# 12_MiniPcie-4G.net
KiCad netlist of a schematic drawn in Altium Designer
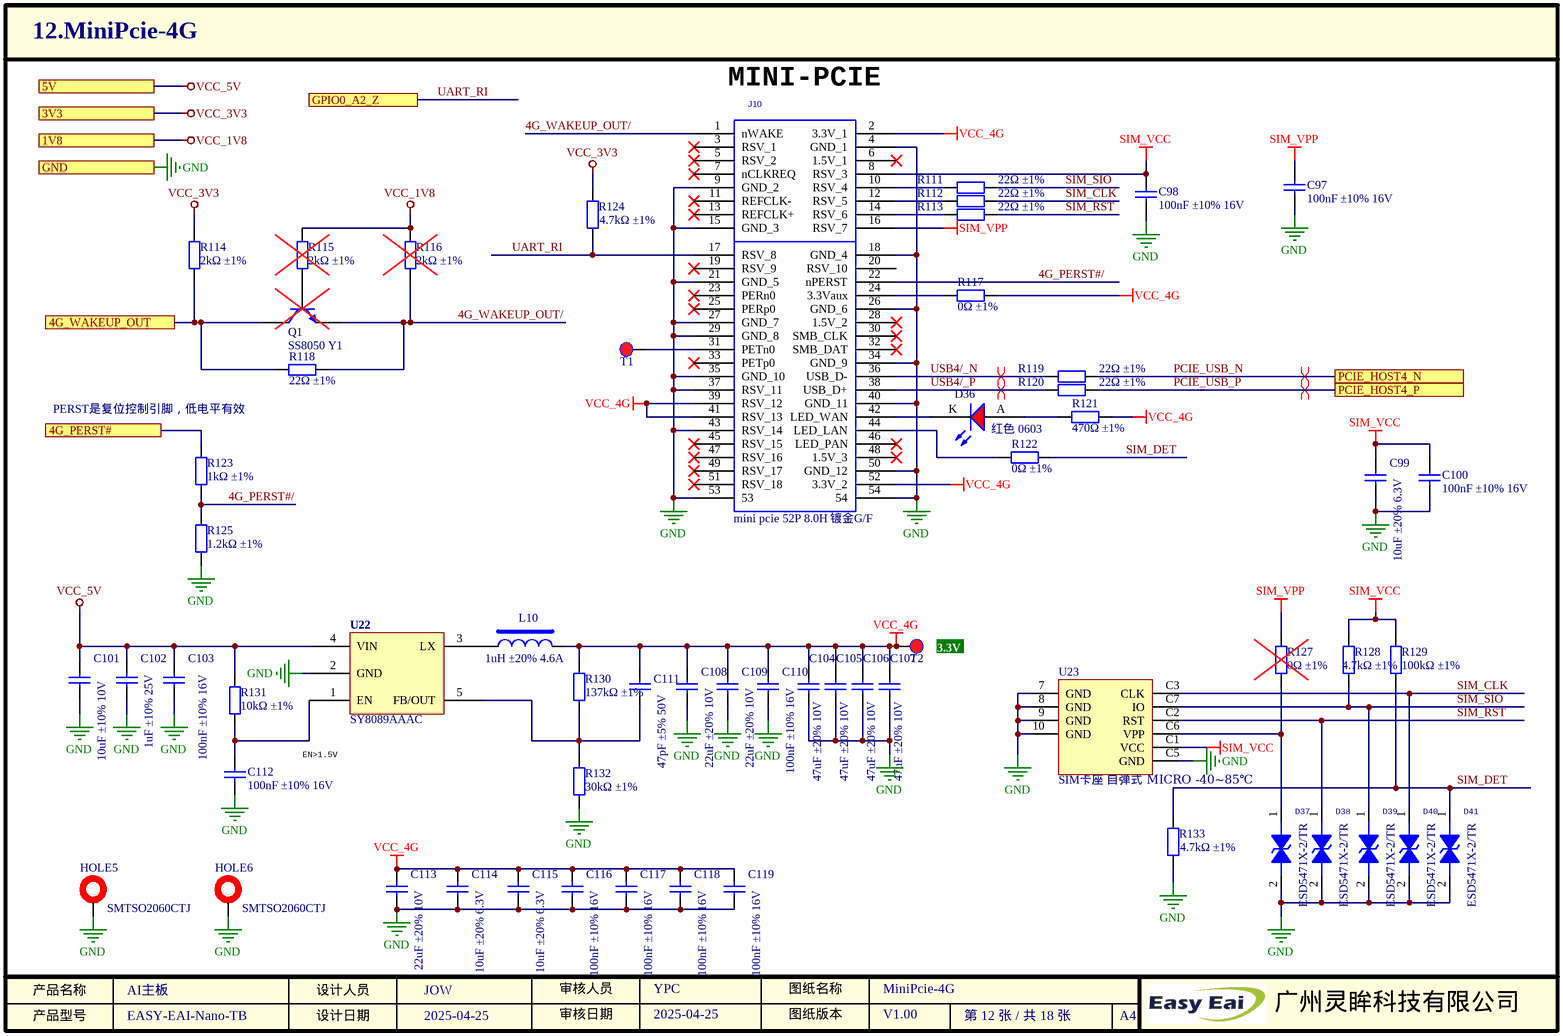
[diagram p0: 12.MiniPcie-4G.SchDoc]

(export (version "E")
  (design (tool "Eeschema 10.0.6"))
  (components
    (comp (ref "C97")
      (value "CL05B104KO5NNNC")
      (footprint "0402_C")
      (description "SPZL000259")
      (fields (field (name "描述") "100nF ±10% 16V"))
      (libsource (lib "CAP_EASY-EAI") (part "0402 100nF ±10% 16V"))
    )
    (comp (ref "C98")
      (value "CL05B104KO5NNNC")
      (footprint "0402_C")
      (description "SPZL000259")
      (fields (field (name "描述") "100nF ±10% 16V"))
      (libsource (lib "CAP_EASY-EAI") (part "0402 100nF ±10% 16V"))
    )
    (comp (ref "C99")
      (value "CL05A106MQ5NUNC")
      (footprint "0402_C")
      (description "SPZL000269")
      (fields (field (name "描述") "10uF ±20% 6.3V"))
      (libsource (lib "CAP_EASY-EAI") (part "0402 10uF ±20% 6.3V"))
    )
    (comp (ref "C100")
      (value "CL05B104KO5NNNC")
      (footprint "0402_C")
      (description "SPZL000259")
      (fields (field (name "描述") "100nF ±10% 16V"))
      (libsource (lib "CAP_EASY-EAI") (part "0402 100nF ±10% 16V"))
    )
    (comp (ref "C101")
      (value "CL10A106KP8NNNC")
      (footprint "0603_C")
      (description "SPZL000260")
      (fields (field (name "描述") "10uF ±10% 10V"))
      (libsource (lib "CAP_lexing") (part "0603 10uF ±10% 10V"))
    )
    (comp (ref "C102")
      (value "CL05A105KA5NQNC")
      (footprint "0402_C")
      (description "SPZL000337")
      (fields (field (name "描述") "1uF ±10% 25V"))
      (libsource (lib "CAP_lexing") (part "0402 1uF ±10% 25V"))
    )
    (comp (ref "C103")
      (value "CL05B104KO5NNNC")
      (footprint "0402_C")
      (description "SPZL000259")
      (fields (field (name "描述") "100nF ±10% 16V"))
      (libsource (lib "CAP_lexing") (part "0402 100nF ±10% 16V"))
    )
    (comp (ref "C104")
      (value "C2012X5R1A476MTJ00E")
      (footprint "0805_C")
      (description "SPZL001333")
      (fields (field (name "描述") "47uF ±20% 10V"))
      (libsource (lib "CAP_EASY-EAI") (part "0805 47uF ±20% 10V"))
    )
    (comp (ref "C105")
      (value "C2012X5R1A476MTJ00E")
      (footprint "0805_C")
      (description "SPZL001333")
      (fields (field (name "描述") "47uF ±20% 10V"))
      (libsource (lib "CAP_EASY-EAI") (part "0805 47uF ±20% 10V"))
    )
    (comp (ref "C106")
      (value "C2012X5R1A476MTJ00E")
      (footprint "0805_C")
      (description "SPZL001333")
      (fields (field (name "描述") "47uF ±20% 10V"))
      (libsource (lib "CAP_EASY-EAI") (part "0805 47uF ±20% 10V"))
    )
    (comp (ref "C107")
      (value "C2012X5R1A476MTJ00E")
      (footprint "0805_C")
      (description "SPZL001333")
      (fields (field (name "描述") "47uF ±20% 10V"))
      (libsource (lib "CAP_EASY-EAI") (part "0805 47uF ±20% 10V"))
    )
    (comp (ref "C108")
      (value "CL10A226MP8NUNE")
      (footprint "0603_C")
      (description "SPZL000315")
      (fields (field (name "描述") "22uF ±20% 10V"))
      (libsource (lib "CAP_lexing") (part "0603 22uF ±20% 10V"))
    )
    (comp (ref "C109")
      (value "CL10A226MP8NUNE")
      (footprint "0603_C")
      (description "SPZL000315")
      (fields (field (name "描述") "22uF ±20% 10V"))
      (libsource (lib "CAP_lexing") (part "0603 22uF ±20% 10V"))
    )
    (comp (ref "C110")
      (value "CL05B104KO5NNNC")
      (footprint "0402_C")
      (description "SPZL000259")
      (fields (field (name "描述") "100nF ±10% 16V"))
      (libsource (lib "CAP_lexing") (part "0402 100nF ±10% 16V"))
    )
    (comp (ref "C111")
      (value "NC/0402CG470J500NT")
      (footprint "0402_C")
      (description "SPZL000882")
      (fields (field (name "描述") "47pF ±5% 50V"))
      (libsource (lib "CAP_lexing") (part "0402 47pF ±5% 50V"))
    )
    (comp (ref "C112")
      (value "CL05B104KO5NNNC")
      (footprint "0402_C")
      (description "SPZL000259")
      (fields (field (name "描述") "100nF ±10% 16V"))
      (libsource (lib "CAP_lexing") (part "0402 100nF ±10% 16V"))
    )
    (comp (ref "C113")
      (value "CL10A226MP8NUNE")
      (footprint "0603_C")
      (description "SPZL000315")
      (fields (field (name "描述") "22uF ±20% 10V"))
      (libsource (lib "CAP_EASY-EAI") (part "0603 22uF ±20% 10V"))
    )
    (comp (ref "C114")
      (value "CL05A106MQ5NUNC")
      (footprint "0402_C")
      (description "SPZL000269")
      (fields (field (name "描述") "10uF ±20% 6.3V"))
      (libsource (lib "CAP_EASY-EAI") (part "0402 10uF ±20% 6.3V"))
    )
    (comp (ref "C115")
      (value "CL05A106MQ5NUNC")
      (footprint "0402_C")
      (description "SPZL000269")
      (fields (field (name "描述") "10uF ±20% 6.3V"))
      (libsource (lib "CAP_EASY-EAI") (part "0402 10uF ±20% 6.3V"))
    )
    (comp (ref "C116")
      (value "CL05B104KO5NNNC")
      (footprint "0402_C")
      (description "SPZL000259")
      (fields (field (name "描述") "100nF ±10% 16V"))
      (libsource (lib "CAP_lexing") (part "0402 100nF ±10% 16V"))
    )
    (comp (ref "C117")
      (value "CL05B104KO5NNNC")
      (footprint "0402_C")
      (description "SPZL000259")
      (fields (field (name "描述") "100nF ±10% 16V"))
      (libsource (lib "CAP_lexing") (part "0402 100nF ±10% 16V"))
    )
    (comp (ref "C118")
      (value "CL05B104KO5NNNC")
      (footprint "0402_C")
      (description "SPZL000259")
      (fields (field (name "描述") "100nF ±10% 16V"))
      (libsource (lib "CAP_lexing") (part "0402 100nF ±10% 16V"))
    )
    (comp (ref "C119")
      (value "CL05B104KO5NNNC")
      (footprint "0402_C")
      (description "SPZL000259")
      (fields (field (name "描述") "100nF ±10% 16V"))
      (libsource (lib "CAP_lexing") (part "0402 100nF ±10% 16V"))
    )
    (comp (ref "D36")
      (value "红色 0603")
      (footprint "0603_LED_S1")
      (description "SPZL000214")
      (fields (field (name "描述") "红色 0603"))
      (libsource (lib "LED_EASY-EAI") (part "红色 0603"))
    )
    (comp (ref "D37")
      (value "ESD5471X-2/TR")
      (footprint "FBP-02C")
      (description "SPZL000254")
      (fields (field (name "型号") "ESD5471X-2/TR"))
      (libsource (lib "ESD_EASY-EAI") (part "TVS ESD5471X-2/TR"))
    )
    (comp (ref "D38")
      (value "ESD5471X-2/TR")
      (footprint "FBP-02C")
      (description "SPZL000254")
      (fields (field (name "型号") "ESD5471X-2/TR"))
      (libsource (lib "ESD_EASY-EAI") (part "TVS ESD5471X-2/TR"))
    )
    (comp (ref "D39")
      (value "ESD5471X-2/TR")
      (footprint "FBP-02C")
      (description "SPZL000254")
      (fields (field (name "型号") "ESD5471X-2/TR"))
      (libsource (lib "ESD_EASY-EAI") (part "TVS ESD5471X-2/TR"))
    )
    (comp (ref "D40")
      (value "ESD5471X-2/TR")
      (footprint "FBP-02C")
      (description "SPZL000254")
      (fields (field (name "型号") "ESD5471X-2/TR"))
      (libsource (lib "ESD_EASY-EAI") (part "TVS ESD5471X-2/TR"))
    )
    (comp (ref "D41")
      (value "ESD5471X-2/TR")
      (footprint "FBP-02C")
      (description "SPZL000254")
      (fields (field (name "型号") "ESD5471X-2/TR"))
      (libsource (lib "ESD_EASY-EAI") (part "TVS ESD5471X-2/TR"))
    )
    (comp (ref "HOLE5")
      (value "SMTSO2060CTJ")
      (footprint "Mou Hole-373D600H-SMD")
      (description "SPZL000166")
      (fields (field (name "型号") "SMTSO2060CTJ"))
      (libsource (lib "Other_lexing") (part "螺柱 SMTSO-M2-6ET"))
    )
    (comp (ref "HOLE6")
      (value "SMTSO2060CTJ")
      (footprint "Mou Hole-373D600H-SMD")
      (description "SPZL000166")
      (fields (field (name "型号") "SMTSO2060CTJ"))
      (libsource (lib "Other_lexing") (part "螺柱 SMTSO-M2-6ET"))
    )
    (comp (ref "J10")
      (value "91304-80-052R2")
      (footprint "MEDC52-32F-PCIE-LOCK-L")
      (description "SPZL000136")
      (fields (field (name "描述") "mini pcie 52P 8.0H 镀金G/F"))
      (libsource (lib "Connector_EASY-EAI") (part "mini pcie 52P 8.0H 镀金G/F"))
    )
    (comp (ref "L10")
      (value "WPN252010U1R0MT")
      (footprint "1008")
      (description "SPZL000872")
      (fields (field (name "描述") "1uH ±20% 4.6A"))
      (libsource (lib "Inductor_lexing") (part "1uH ±20% 4.6A"))
    )
    (comp (ref "Q1")
      (value "NC/SS8050 Y1")
      (footprint "SOT-23(SOT-23-3)")
      (fields (field (name "型号") "SS8050 Y1"))
      (libsource (lib "MOS_lexing") (part "NPN SS8050 Y1"))
    )
    (comp (ref "R111")
      (value "0402WGF220JTCE")
      (footprint "0402_R")
      (description "SPZL000279")
      (fields (field (name "描述") "22Ω ±1%"))
      (libsource (lib "RES_EASY-EAI") (part "0402 22Ω ±1%"))
    )
    (comp (ref "R112")
      (value "0402WGF220JTCE")
      (footprint "0402_R")
      (description "SPZL000279")
      (fields (field (name "描述") "22Ω ±1%"))
      (libsource (lib "RES_EASY-EAI") (part "0402 22Ω ±1%"))
    )
    (comp (ref "R113")
      (value "0402WGF220JTCE")
      (footprint "0402_R")
      (description "SPZL000279")
      (fields (field (name "描述") "22Ω ±1%"))
      (libsource (lib "RES_EASY-EAI") (part "0402 22Ω ±1%"))
    )
    (comp (ref "R114")
      (value "0402WGF2001TCE")
      (footprint "0402_R")
      (description "SPZL000278")
      (fields (field (name "描述") "2kΩ ±1%"))
      (libsource (lib "RES_EASY-EAI") (part "0402 2kΩ ±1%"))
    )
    (comp (ref "R115")
      (value "NC/0402WGF2001TCE")
      (footprint "0402_R")
      (fields (field (name "描述") "2kΩ ±1%"))
      (libsource (lib "RES_lexing") (part "0402 2kΩ ±1%"))
    )
    (comp (ref "R116")
      (value "NC/0402WGF2001TCE")
      (footprint "0402_R")
      (fields (field (name "描述") "2kΩ ±1%"))
      (libsource (lib "RES_lexing") (part "0402 2kΩ ±1%"))
    )
    (comp (ref "R117")
      (value "0402WGF0000TCE")
      (footprint "0402_R")
      (description "SPZL000276")
      (fields (field (name "描述") "0Ω ±1%"))
      (libsource (lib "RES_EASY-EAI") (part "0402 0Ω ±1%"))
    )
    (comp (ref "R118")
      (value "0402WGF220JTCE")
      (footprint "0402_R")
      (description "SPZL000279")
      (fields (field (name "描述") "22Ω ±1%"))
      (libsource (lib "RES_EASY-EAI") (part "0402 22Ω ±1%"))
    )
    (comp (ref "R119")
      (value "0402WGF220JTCE")
      (footprint "0402_R")
      (description "SPZL000279")
      (fields (field (name "描述") "22Ω ±1%"))
      (libsource (lib "RES_EASY-EAI") (part "0402 22Ω ±1%"))
    )
    (comp (ref "R120")
      (value "0402WGF220JTCE")
      (footprint "0402_R")
      (description "SPZL000279")
      (fields (field (name "描述") "22Ω ±1%"))
      (libsource (lib "RES_EASY-EAI") (part "0402 22Ω ±1%"))
    )
    (comp (ref "R121")
      (value "AC0402FR-07470RL")
      (footprint "0402_R")
      (description "SPZL000329")
      (fields (field (name "描述") "470Ω ±1%"))
      (libsource (lib "RES_EASY-EAI") (part "0402 470Ω ±1%"))
    )
    (comp (ref "R122")
      (value "0402WGF0000TCE")
      (footprint "0402_R")
      (description "SPZL000276")
      (fields (field (name "描述") "0Ω ±1%"))
      (libsource (lib "RES_EASY-EAI") (part "0402 0Ω ±1%"))
    )
    (comp (ref "R123")
      (value "0402WGF1001TCE")
      (footprint "0402_R")
      (description "SPZL000275")
      (fields (field (name "描述") "1kΩ ±1%"))
      (libsource (lib "RES_EASY-EAI") (part "0402 1kΩ ±1%"))
    )
    (comp (ref "R124")
      (value "0402WGF4701TCE")
      (footprint "0402_R")
      (description "SPZL000280")
      (fields (field (name "描述") "4.7kΩ ±1%"))
      (libsource (lib "RES_EASY-EAI") (part "0402 4.7kΩ ±1%"))
    )
    (comp (ref "R125")
      (value "AC0402FR-071K2L")
      (footprint "0402_R")
      (description "SPZL000328")
      (fields (field (name "描述") "1.2kΩ ±1%"))
      (libsource (lib "RES_EASY-EAI") (part "0402 1.2kΩ ±1%"))
    )
    (comp (ref "R127")
      (value "NC/0402WGF0000TCE")
      (footprint "0402_R")
      (fields (field (name "描述") "0Ω ±1%"))
      (libsource (lib "RES_lexing") (part "0402 0Ω ±1%"))
    )
    (comp (ref "R128")
      (value "0402WGF4701TCE")
      (footprint "0402_R")
      (description "SPZL000280")
      (fields (field (name "描述") "4.7kΩ ±1%"))
      (libsource (lib "RES_EASY-EAI") (part "0402 4.7kΩ ±1%"))
    )
    (comp (ref "R129")
      (value "0402WGF1003TCE")
      (footprint "0402_R")
      (description "SPZL000282")
      (fields (field (name "描述") "100kΩ ±1%"))
      (libsource (lib "RES_EASY-EAI") (part "0402 100kΩ ±1%"))
    )
    (comp (ref "R130")
      (value "0402WGF1373TCE")
      (footprint "0402_R")
      (description "SPZL000322")
      (fields (field (name "描述") "137kΩ ±1%"))
      (libsource (lib "RES_EASY-EAI") (part "0402 137kΩ ±1%"))
    )
    (comp (ref "R131")
      (value "0402WGF1002TCE")
      (footprint "0402_R")
      (description "SPZL000271")
      (fields (field (name "描述") "10kΩ ±1%"))
      (libsource (lib "RES_lexing") (part "0402 10kΩ ±1%"))
    )
    (comp (ref "R132")
      (value "NQ02WGF3002TCE")
      (footprint "0402_R")
      (description "SPZL000323")
      (fields (field (name "描述") "30kΩ ±1%"))
      (libsource (lib "RES_EASY-EAI") (part "0402 30kΩ ±1%"))
    )
    (comp (ref "R133")
      (value "0402WGF4701TCE")
      (footprint "0402_R")
      (description "SPZL000280")
      (fields (field (name "描述") "4.7kΩ ±1%"))
      (libsource (lib "RES_EASY-EAI") (part "0402 4.7kΩ ±1%"))
    )
    (comp (ref "T1")
      (value "TEST-DOT")
      (footprint "PAD-25/40")
      (libsource (lib "Other_lexing") (part "TEST-DOT"))
    )
    (comp (ref "T2")
      (value "TEST-DOT")
      (footprint "PAD-25/40")
      (libsource (lib "Other_lexing") (part "TEST-DOT"))
    )
    (comp (ref "U22")
      (value "SY8089AAAC")
      (footprint "SOT-23-5")
      (description "SPZL000040")
      (fields (field (name "型号") "SY8089AAAC"))
      (libsource (lib "Power_EASY-EAI") (part "SY8089AAAC"))
    )
    (comp (ref "U23")
      (value "SMC-202-6")
      (footprint "SIM-SMD_SMC-202-6")
      (description "SPZL001068")
      (fields (field (name "描述") "SIM卡座 自弹式 MICRO -40~85℃"))
      (libsource (lib "EVBoard-RK3562_1") (part "SIM卡座 自弹式 MICRO"))
    )
  )
  (nets
    (net (code "1") (name "/4G_PERST#") (class "Default")
      (node (ref "R123") (pin "2") (pinfunction "2_2") (pintype "passive"))
    )
    (net (code "2") (name "/4G_PERST#{slash}") (class "Default")
      (node (ref "J10") (pin "22") (pinfunction "nPERST_22") (pintype "passive"))
      (node (ref "R123") (pin "1") (pinfunction "1_1") (pintype "passive"))
      (node (ref "R125") (pin "2") (pinfunction "2_2") (pintype "passive"))
    )
    (net (code "3") (name "/4G_WAKEUP_OUT") (class "Default")
      (node (ref "Q1") (pin "3") (pinfunction "C_3") (pintype "passive"))
      (node (ref "R114") (pin "1") (pinfunction "1_1") (pintype "passive"))
      (node (ref "R118") (pin "1") (pinfunction "1_1") (pintype "passive"))
    )
    (net (code "4") (name "/4G_WAKEUP_OUT{slash}") (class "Default")
      (node (ref "J10") (pin "1") (pinfunction "nWAKE_1") (pintype "passive"))
      (node (ref "Q1") (pin "2") (pinfunction "E_2") (pintype "passive"))
      (node (ref "R116") (pin "1") (pinfunction "1_1") (pintype "passive"))
      (node (ref "R118") (pin "2") (pinfunction "2_2") (pintype "passive"))
    )
    (net (code "5") (name "/PCIE_USB_N") (class "Default")
      (node (ref "R119") (pin "2") (pinfunction "2_2") (pintype "passive"))
    )
    (net (code "6") (name "/PCIE_USB_P") (class "Default")
      (node (ref "R120") (pin "2") (pinfunction "2_2") (pintype "passive"))
    )
    (net (code "7") (name "/SIM_CLK") (class "Default")
      (node (ref "D40") (pin "1") (pinfunction "1_1") (pintype "passive"))
      (node (ref "R112") (pin "2") (pinfunction "2_2") (pintype "passive"))
      (node (ref "U23") (pin "C3") (pinfunction "CLK_C3") (pintype "passive"))
    )
    (net (code "8") (name "/SIM_DET") (class "Default")
      (node (ref "D41") (pin "1") (pinfunction "1_1") (pintype "passive"))
      (node (ref "R122") (pin "2") (pinfunction "2_2") (pintype "passive"))
      (node (ref "R129") (pin "1") (pinfunction "1_1") (pintype "passive"))
      (node (ref "R133") (pin "2") (pinfunction "2_2") (pintype "passive"))
    )
    (net (code "9") (name "/SIM_RST") (class "Default")
      (node (ref "D38") (pin "1") (pinfunction "1_1") (pintype "passive"))
      (node (ref "R113") (pin "2") (pinfunction "2_2") (pintype "passive"))
      (node (ref "U23") (pin "C2") (pinfunction "RST_C2") (pintype "passive"))
    )
    (net (code "10") (name "/SIM_SIO") (class "Default")
      (node (ref "D39") (pin "1") (pinfunction "1_1") (pintype "passive"))
      (node (ref "R111") (pin "2") (pinfunction "2_2") (pintype "passive"))
      (node (ref "R128") (pin "1") (pinfunction "1_1") (pintype "passive"))
      (node (ref "U23") (pin "C7") (pinfunction "IO_C7") (pintype "passive"))
    )
    (net (code "11") (name "/UART_RI") (class "Default")
      (node (ref "J10") (pin "17") (pinfunction "RSV_8_17") (pintype "passive"))
      (node (ref "R124") (pin "1") (pinfunction "1_1") (pintype "passive"))
    )
    (net (code "12") (name "/USB4{slash}_N") (class "Default")
      (node (ref "J10") (pin "36") (pinfunction "USB_D-_36") (pintype "passive"))
      (node (ref "R119") (pin "1") (pinfunction "1_1") (pintype "passive"))
    )
    (net (code "13") (name "/USB4{slash}_P") (class "Default")
      (node (ref "J10") (pin "38") (pinfunction "USB_D+_38") (pintype "passive"))
      (node (ref "R120") (pin "1") (pinfunction "1_1") (pintype "passive"))
    )
    (net (code "14") (name "GND") (class "Default")
      (node (ref "C100") (pin "1") (pinfunction "1_1") (pintype "passive"))
      (node (ref "C101") (pin "1") (pinfunction "1_1") (pintype "passive"))
      (node (ref "C102") (pin "1") (pinfunction "1_1") (pintype "passive"))
      (node (ref "C103") (pin "1") (pinfunction "1_1") (pintype "passive"))
      (node (ref "C104") (pin "1") (pinfunction "1_1") (pintype "passive"))
      (node (ref "C105") (pin "1") (pinfunction "1_1") (pintype "passive"))
      (node (ref "C106") (pin "1") (pinfunction "1_1") (pintype "passive"))
      (node (ref "C107") (pin "1") (pinfunction "1_1") (pintype "passive"))
      (node (ref "C108") (pin "1") (pinfunction "1_1") (pintype "passive"))
      (node (ref "C109") (pin "1") (pinfunction "1_1") (pintype "passive"))
      (node (ref "C110") (pin "1") (pinfunction "1_1") (pintype "passive"))
      (node (ref "C112") (pin "1") (pinfunction "1_1") (pintype "passive"))
      (node (ref "C113") (pin "1") (pinfunction "1_1") (pintype "passive"))
      (node (ref "C114") (pin "1") (pinfunction "1_1") (pintype "passive"))
      (node (ref "C115") (pin "1") (pinfunction "1_1") (pintype "passive"))
      (node (ref "C116") (pin "1") (pinfunction "1_1") (pintype "passive"))
      (node (ref "C117") (pin "1") (pinfunction "1_1") (pintype "passive"))
      (node (ref "C118") (pin "1") (pinfunction "1_1") (pintype "passive"))
      (node (ref "C119") (pin "1") (pinfunction "1_1") (pintype "passive"))
      (node (ref "C97") (pin "1") (pinfunction "1_1") (pintype "passive"))
      (node (ref "C98") (pin "1") (pinfunction "1_1") (pintype "passive"))
      (node (ref "C99") (pin "1") (pinfunction "1_1") (pintype "passive"))
      (node (ref "D37") (pin "2") (pinfunction "2_2") (pintype "passive"))
      (node (ref "D38") (pin "2") (pinfunction "2_2") (pintype "passive"))
      (node (ref "D39") (pin "2") (pinfunction "2_2") (pintype "passive"))
      (node (ref "D40") (pin "2") (pinfunction "2_2") (pintype "passive"))
      (node (ref "D41") (pin "2") (pinfunction "2_2") (pintype "passive"))
      (node (ref "HOLE5") (pin "1") (pintype "passive"))
      (node (ref "HOLE6") (pin "1") (pintype "passive"))
      (node (ref "J10") (pin "15") (pinfunction "GND_3_15") (pintype "passive"))
      (node (ref "J10") (pin "18") (pinfunction "GND_4_18") (pintype "passive"))
      (node (ref "J10") (pin "21") (pinfunction "GND_5_21") (pintype "passive"))
      (node (ref "J10") (pin "26") (pinfunction "GND_6_26") (pintype "passive"))
      (node (ref "J10") (pin "27") (pinfunction "GND_7_27") (pintype "passive"))
      (node (ref "J10") (pin "29") (pinfunction "GND_8_29") (pintype "passive"))
      (node (ref "J10") (pin "34") (pinfunction "GND_9_34") (pintype "passive"))
      (node (ref "J10") (pin "35") (pinfunction "GND_10_35") (pintype "passive"))
      (node (ref "J10") (pin "37") (pinfunction "RSV_11_37") (pintype "passive"))
      (node (ref "J10") (pin "4") (pinfunction "GND_1_4") (pintype "passive"))
      (node (ref "J10") (pin "40") (pinfunction "GND_11_40") (pintype "passive"))
      (node (ref "J10") (pin "43") (pinfunction "RSV_14_43") (pintype "passive"))
      (node (ref "J10") (pin "50") (pinfunction "GND_12_50") (pintype "passive"))
      (node (ref "J10") (pin "53") (pinfunction "53_53") (pintype "passive"))
      (node (ref "J10") (pin "54") (pinfunction "54_54") (pintype "passive"))
      (node (ref "J10") (pin "9") (pinfunction "GND_2_9") (pintype "passive"))
      (node (ref "R125") (pin "1") (pinfunction "1_1") (pintype "passive"))
      (node (ref "R132") (pin "1") (pinfunction "1_1") (pintype "passive"))
      (node (ref "R133") (pin "1") (pinfunction "1_1") (pintype "passive"))
      (node (ref "U22") (pin "2") (pinfunction "GND_2") (pintype "passive"))
      (node (ref "U23") (pin "10") (pinfunction "GND_10") (pintype "passive"))
      (node (ref "U23") (pin "7") (pinfunction "GND_7") (pintype "passive"))
      (node (ref "U23") (pin "8") (pinfunction "GND_8") (pintype "passive"))
      (node (ref "U23") (pin "9") (pinfunction "GND_9") (pintype "passive"))
      (node (ref "U23") (pin "C5") (pinfunction "GND_C5") (pintype "passive"))
    )
    (net (code "15") (name "Net-(D36-PadA)") (class "Default")
      (node (ref "D36") (pin "A") (pinfunction "A_A") (pintype "passive"))
      (node (ref "R121") (pin "1") (pinfunction "1_1") (pintype "passive"))
    )
    (net (code "16") (name "Net-(J10-3.3Vaux)") (class "Default")
      (node (ref "J10") (pin "24") (pinfunction "3.3Vaux_24") (pintype "passive"))
      (node (ref "R117") (pin "1") (pinfunction "1_1") (pintype "passive"))
    )
    (net (code "17") (name "Net-(J10-LED_LAN)") (class "Default")
      (node (ref "J10") (pin "44") (pinfunction "LED_LAN_44") (pintype "passive"))
      (node (ref "R122") (pin "1") (pinfunction "1_1") (pintype "passive"))
    )
    (net (code "18") (name "Net-(J10-LED_WAN)") (class "Default")
      (node (ref "D36") (pin "K") (pinfunction "K_K") (pintype "passive"))
      (node (ref "J10") (pin "42") (pinfunction "LED_WAN_42") (pintype "passive"))
    )
    (net (code "19") (name "Net-(J10-PETn0)") (class "Default")
      (node (ref "J10") (pin "31") (pinfunction "PETn0_31") (pintype "passive"))
      (node (ref "T1") (pin "1") (pinfunction "1_1") (pintype "passive"))
    )
    (net (code "20") (name "Net-(J10-RSV_4)") (class "Default")
      (node (ref "J10") (pin "10") (pinfunction "RSV_4_10") (pintype "passive"))
      (node (ref "R111") (pin "1") (pinfunction "1_1") (pintype "passive"))
    )
    (net (code "21") (name "Net-(J10-RSV_5)") (class "Default")
      (node (ref "J10") (pin "12") (pinfunction "RSV_5_12") (pintype "passive"))
      (node (ref "R112") (pin "1") (pinfunction "1_1") (pintype "passive"))
    )
    (net (code "22") (name "Net-(J10-RSV_6)") (class "Default")
      (node (ref "J10") (pin "14") (pinfunction "RSV_6_14") (pintype "passive"))
      (node (ref "R113") (pin "1") (pinfunction "1_1") (pintype "passive"))
    )
    (net (code "23") (name "Net-(Q1-B)") (class "Default")
      (node (ref "Q1") (pin "1") (pinfunction "B_1") (pintype "passive"))
      (node (ref "R115") (pin "1") (pinfunction "1_1") (pintype "passive"))
    )
    (net (code "24") (name "Net-(U22-EN)") (class "Default")
      (node (ref "C112") (pin "2") (pinfunction "2_2") (pintype "passive"))
      (node (ref "R131") (pin "1") (pinfunction "1_1") (pintype "passive"))
      (node (ref "U22") (pin "1") (pinfunction "EN_1") (pintype "passive"))
    )
    (net (code "25") (name "Net-(U22-FB{slash}OUT)") (class "Default")
      (node (ref "C111") (pin "1") (pinfunction "1_1") (pintype "passive"))
      (node (ref "R130") (pin "1") (pinfunction "1_1") (pintype "passive"))
      (node (ref "R132") (pin "2") (pinfunction "2_2") (pintype "passive"))
      (node (ref "U22") (pin "5") (pinfunction "FB/OUT_5") (pintype "passive"))
    )
    (net (code "26") (name "Net-(U22-LX)") (class "Default")
      (node (ref "L10") (pin "1") (pinfunction "1_1") (pintype "passive"))
      (node (ref "U22") (pin "3") (pinfunction "LX_3") (pintype "passive"))
    )
    (net (code "27") (name "Net-(U23-VPP)") (class "Default")
      (node (ref "D37") (pin "1") (pinfunction "1_1") (pintype "passive"))
      (node (ref "R127") (pin "1") (pinfunction "1_1") (pintype "passive"))
      (node (ref "U23") (pin "C6") (pinfunction "VPP_C6") (pintype "passive"))
    )
    (net (code "28") (name "SIM_VCC") (class "Default")
      (node (ref "C100") (pin "2") (pinfunction "2_2") (pintype "passive"))
      (node (ref "C98") (pin "2") (pinfunction "2_2") (pintype "passive"))
      (node (ref "C99") (pin "2") (pinfunction "2_2") (pintype "passive"))
      (node (ref "J10") (pin "8") (pinfunction "RSV_3_8") (pintype "passive"))
      (node (ref "R128") (pin "2") (pinfunction "2_2") (pintype "passive"))
      (node (ref "R129") (pin "2") (pinfunction "2_2") (pintype "passive"))
      (node (ref "U23") (pin "C1") (pinfunction "VCC_C1") (pintype "passive"))
    )
    (net (code "29") (name "SIM_VPP") (class "Default")
      (node (ref "C97") (pin "2") (pinfunction "2_2") (pintype "passive"))
      (node (ref "J10") (pin "16") (pinfunction "RSV_7_16") (pintype "passive"))
      (node (ref "R127") (pin "2") (pinfunction "2_2") (pintype "passive"))
    )
    (net (code "30") (name "VCC_1V8") (class "Default")
      (node (ref "R115") (pin "2") (pinfunction "2_2") (pintype "passive"))
      (node (ref "R116") (pin "2") (pinfunction "2_2") (pintype "passive"))
    )
    (net (code "31") (name "VCC_3V3") (class "Default")
      (node (ref "R114") (pin "2") (pinfunction "2_2") (pintype "passive"))
      (node (ref "R124") (pin "2") (pinfunction "2_2") (pintype "passive"))
    )
    (net (code "32") (name "VCC_4G") (class "Default")
      (node (ref "C104") (pin "2") (pinfunction "2_2") (pintype "passive"))
      (node (ref "C105") (pin "2") (pinfunction "2_2") (pintype "passive"))
      (node (ref "C106") (pin "2") (pinfunction "2_2") (pintype "passive"))
      (node (ref "C107") (pin "2") (pinfunction "2_2") (pintype "passive"))
      (node (ref "C108") (pin "2") (pinfunction "2_2") (pintype "passive"))
      (node (ref "C109") (pin "2") (pinfunction "2_2") (pintype "passive"))
      (node (ref "C110") (pin "2") (pinfunction "2_2") (pintype "passive"))
      (node (ref "C111") (pin "2") (pinfunction "2_2") (pintype "passive"))
      (node (ref "C113") (pin "2") (pinfunction "2_2") (pintype "passive"))
      (node (ref "C114") (pin "2") (pinfunction "2_2") (pintype "passive"))
      (node (ref "C115") (pin "2") (pinfunction "2_2") (pintype "passive"))
      (node (ref "C116") (pin "2") (pinfunction "2_2") (pintype "passive"))
      (node (ref "C117") (pin "2") (pinfunction "2_2") (pintype "passive"))
      (node (ref "C118") (pin "2") (pinfunction "2_2") (pintype "passive"))
      (node (ref "C119") (pin "2") (pinfunction "2_2") (pintype "passive"))
      (node (ref "J10") (pin "2") (pinfunction "3.3V_1_2") (pintype "passive"))
      (node (ref "J10") (pin "39") (pinfunction "RSV_12_39") (pintype "passive"))
      (node (ref "J10") (pin "41") (pinfunction "RSV_13_41") (pintype "passive"))
      (node (ref "J10") (pin "52") (pinfunction "3.3V_2_52") (pintype "passive"))
      (node (ref "L10") (pin "2") (pinfunction "2_2") (pintype "passive"))
      (node (ref "R117") (pin "2") (pinfunction "2_2") (pintype "passive"))
      (node (ref "R121") (pin "2") (pinfunction "2_2") (pintype "passive"))
      (node (ref "R130") (pin "2") (pinfunction "2_2") (pintype "passive"))
      (node (ref "T2") (pin "1") (pinfunction "1_1") (pintype "passive"))
    )
    (net (code "33") (name "VCC_5V") (class "Default")
      (node (ref "C101") (pin "2") (pinfunction "2_2") (pintype "passive"))
      (node (ref "C102") (pin "2") (pinfunction "2_2") (pintype "passive"))
      (node (ref "C103") (pin "2") (pinfunction "2_2") (pintype "passive"))
      (node (ref "R131") (pin "2") (pinfunction "2_2") (pintype "passive"))
      (node (ref "U22") (pin "4") (pinfunction "VIN_4") (pintype "passive"))
    )
    (net (code "34") (name "unconnected-(J10-1.5V_1-Pad6)") (class "Default")
      (node (ref "J10") (pin "6") (pinfunction "1.5V_1_6") (pintype "passive+no_connect"))
    )
    (net (code "35") (name "unconnected-(J10-1.5V_2-Pad28)") (class "Default")
      (node (ref "J10") (pin "28") (pinfunction "1.5V_2_28") (pintype "passive+no_connect"))
    )
    (net (code "36") (name "unconnected-(J10-1.5V_3-Pad48)") (class "Default")
      (node (ref "J10") (pin "48") (pinfunction "1.5V_3_48") (pintype "passive+no_connect"))
    )
    (net (code "37") (name "unconnected-(J10-LED_PAN-Pad46)") (class "Default")
      (node (ref "J10") (pin "46") (pinfunction "LED_PAN_46") (pintype "passive+no_connect"))
    )
    (net (code "38") (name "unconnected-(J10-PERn0-Pad23)") (class "Default")
      (node (ref "J10") (pin "23") (pinfunction "PERn0_23") (pintype "passive+no_connect"))
    )
    (net (code "39") (name "unconnected-(J10-PERp0-Pad25)") (class "Default")
      (node (ref "J10") (pin "25") (pinfunction "PERp0_25") (pintype "passive+no_connect"))
    )
    (net (code "40") (name "unconnected-(J10-PETp0-Pad33)") (class "Default")
      (node (ref "J10") (pin "33") (pinfunction "PETp0_33") (pintype "passive+no_connect"))
    )
    (net (code "41") (name "unconnected-(J10-REFCLK+-Pad13)") (class "Default")
      (node (ref "J10") (pin "13") (pinfunction "REFCLK+_13") (pintype "passive+no_connect"))
    )
    (net (code "42") (name "unconnected-(J10-REFCLK--Pad11)") (class "Default")
      (node (ref "J10") (pin "11") (pinfunction "REFCLK-_11") (pintype "passive+no_connect"))
    )
    (net (code "43") (name "unconnected-(J10-RSV_1-Pad3)") (class "Default")
      (node (ref "J10") (pin "3") (pinfunction "RSV_1_3") (pintype "passive+no_connect"))
    )
    (net (code "44") (name "unconnected-(J10-RSV_2-Pad5)") (class "Default")
      (node (ref "J10") (pin "5") (pinfunction "RSV_2_5") (pintype "passive+no_connect"))
    )
    (net (code "45") (name "unconnected-(J10-RSV_9-Pad19)") (class "Default")
      (node (ref "J10") (pin "19") (pinfunction "RSV_9_19") (pintype "passive+no_connect"))
    )
    (net (code "46") (name "unconnected-(J10-RSV_10-Pad20)") (class "Default")
      (node (ref "J10") (pin "20") (pinfunction "RSV_10_20") (pintype "passive"))
    )
    (net (code "47") (name "unconnected-(J10-RSV_15-Pad45)") (class "Default")
      (node (ref "J10") (pin "45") (pinfunction "RSV_15_45") (pintype "passive+no_connect"))
    )
    (net (code "48") (name "unconnected-(J10-RSV_16-Pad47)") (class "Default")
      (node (ref "J10") (pin "47") (pinfunction "RSV_16_47") (pintype "passive+no_connect"))
    )
    (net (code "49") (name "unconnected-(J10-RSV_17-Pad49)") (class "Default")
      (node (ref "J10") (pin "49") (pinfunction "RSV_17_49") (pintype "passive+no_connect"))
    )
    (net (code "50") (name "unconnected-(J10-RSV_18-Pad51)") (class "Default")
      (node (ref "J10") (pin "51") (pinfunction "RSV_18_51") (pintype "passive+no_connect"))
    )
    (net (code "51") (name "unconnected-(J10-SMB_CLK-Pad30)") (class "Default")
      (node (ref "J10") (pin "30") (pinfunction "SMB_CLK_30") (pintype "passive+no_connect"))
    )
    (net (code "52") (name "unconnected-(J10-SMB_DAT-Pad32)") (class "Default")
      (node (ref "J10") (pin "32") (pinfunction "SMB_DAT_32") (pintype "passive+no_connect"))
    )
    (net (code "53") (name "unconnected-(J10-nCLKREQ-Pad7)") (class "Default")
      (node (ref "J10") (pin "7") (pinfunction "nCLKREQ_7") (pintype "passive+no_connect"))
    )
  )
)
